# Basic_diff_probe.net
KiCad netlist of a schematic drawn in Altium Designer
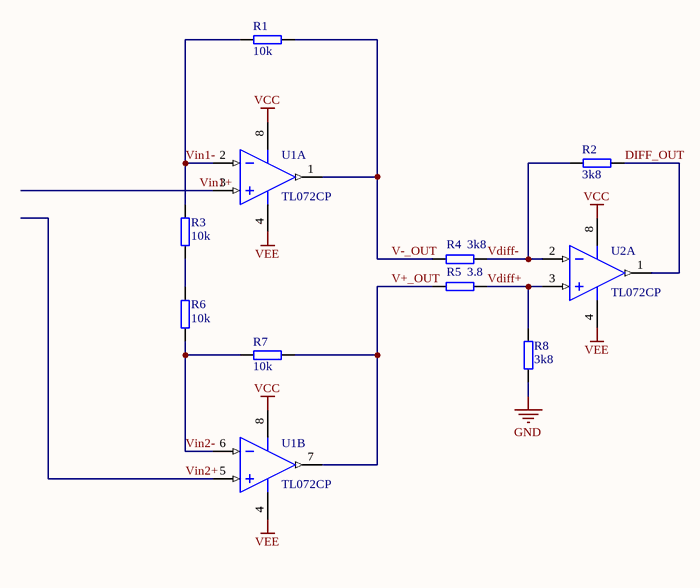
[diagram p0: Basic diff probe.SchDoc]

(export (version "E")
  (design (tool "Eeschema 10.0.6"))
  (components
    (comp (ref "R1")
      (value "10k")
      (footprint "C_CERAMIC_TH_P5.08mm")
      (description "TH, Through Hole")
      (libsource (lib "DiffProbe") (part "Resistor"))
    )
    (comp (ref "R2")
      (value "3k8")
      (footprint "C_CERAMIC_TH_P5.08mm")
      (description "TH, Through Hole")
      (libsource (lib "DiffProbe") (part "Resistor"))
    )
    (comp (ref "R3")
      (value "10k")
      (footprint "C_CERAMIC_TH_P5.08mm")
      (description "TH, Through Hole")
      (libsource (lib "DiffProbe") (part "Resistor"))
    )
    (comp (ref "R4")
      (value "3k8")
      (footprint "C_CERAMIC_TH_P5.08mm")
      (description "TH, Through Hole")
      (libsource (lib "DiffProbe") (part "Resistor"))
    )
    (comp (ref "R5")
      (value "3.8")
      (footprint "C_CERAMIC_TH_P5.08mm")
      (description "TH, Through Hole")
      (libsource (lib "DiffProbe") (part "Resistor"))
    )
    (comp (ref "R6")
      (value "10k")
      (footprint "C_CERAMIC_TH_P5.08mm")
      (description "TH, Through Hole")
      (libsource (lib "DiffProbe") (part "Resistor"))
    )
    (comp (ref "R7")
      (value "10k")
      (footprint "C_CERAMIC_TH_P5.08mm")
      (description "TH, Through Hole")
      (libsource (lib "DiffProbe") (part "Resistor"))
    )
    (comp (ref "R8")
      (value "3k8")
      (footprint "C_CERAMIC_TH_P5.08mm")
      (description "TH, Through Hole")
      (libsource (lib "DiffProbe") (part "Resistor"))
    )
    (comp (ref "U1")
      (value "TL072CP")
      (footprint "P0008A")
      (description "IC OPAMP JFET 3MHZ 8DIP")
      (fields (field (name "MANUFACTURER") "Texas Instruments"))
      (libsource (lib "DiffProbe") (part "TL072CP"))
    )
    (comp (ref "U2")
      (value "TL072CP")
      (footprint "P0008A")
      (description "IC OPAMP JFET 3MHZ 8DIP")
      (fields (field (name "MANUFACTURER") "Texas Instruments"))
      (libsource (lib "DiffProbe") (part "TL072CP"))
    )
  )
  (nets
    (net (code "1") (name "/DIFF_OUT") (class "Default")
      (node (ref "R2") (pin "2") (pinfunction "2_2") (pintype "passive"))
      (node (ref "U2") (pin "1") (pinfunction "OUT1_1") (pintype "output"))
    )
    (net (code "2") (name "/V+_OUT") (class "Default")
      (node (ref "R5") (pin "1") (pinfunction "1_1") (pintype "passive"))
      (node (ref "R7") (pin "2") (pinfunction "2_2") (pintype "passive"))
      (node (ref "U1") (pin "7") (pinfunction "OUT2_7") (pintype "output"))
    )
    (net (code "3") (name "/V-_OUT") (class "Default")
      (node (ref "R1") (pin "2") (pinfunction "2_2") (pintype "passive"))
      (node (ref "R4") (pin "1") (pinfunction "1_1") (pintype "passive"))
      (node (ref "U1") (pin "1") (pinfunction "OUT1_1") (pintype "output"))
    )
    (net (code "4") (name "/Vdiff+") (class "Default")
      (node (ref "R5") (pin "2") (pinfunction "2_2") (pintype "passive"))
      (node (ref "R8") (pin "2") (pinfunction "2_2") (pintype "passive"))
      (node (ref "U2") (pin "3") (pinfunction "IN1+_3") (pintype "input"))
    )
    (net (code "5") (name "/Vdiff-") (class "Default")
      (node (ref "R2") (pin "1") (pinfunction "1_1") (pintype "passive"))
      (node (ref "R4") (pin "2") (pinfunction "2_2") (pintype "passive"))
      (node (ref "U2") (pin "2") (pinfunction "IN1-_2") (pintype "input"))
    )
    (net (code "6") (name "/Vin1+") (class "Default")
      (node (ref "U1") (pin "3") (pinfunction "IN1+_3") (pintype "input"))
    )
    (net (code "7") (name "/Vin1-") (class "Default")
      (node (ref "R1") (pin "1") (pinfunction "1_1") (pintype "passive"))
      (node (ref "R3") (pin "2") (pinfunction "2_2") (pintype "passive"))
      (node (ref "U1") (pin "2") (pinfunction "IN1-_2") (pintype "input"))
    )
    (net (code "8") (name "/Vin2+") (class "Default")
      (node (ref "U1") (pin "5") (pinfunction "IN1+_5") (pintype "input"))
    )
    (net (code "9") (name "/Vin2-") (class "Default")
      (node (ref "R6") (pin "1") (pinfunction "1_1") (pintype "passive"))
      (node (ref "R7") (pin "1") (pinfunction "1_1") (pintype "passive"))
      (node (ref "U1") (pin "6") (pinfunction "IN1-_6") (pintype "input"))
    )
    (net (code "10") (name "GND") (class "Default")
      (node (ref "R8") (pin "1") (pinfunction "1_1") (pintype "passive"))
    )
    (net (code "11") (name "Net-(R3-Pad1)") (class "Default")
      (node (ref "R3") (pin "1") (pinfunction "1_1") (pintype "passive"))
      (node (ref "R6") (pin "2") (pinfunction "2_2") (pintype "passive"))
    )
    (net (code "12") (name "VCC") (class "Default")
      (node (ref "U1") (pin "8") (pinfunction "VCC+_8") (pintype "power_in"))
      (node (ref "U2") (pin "8") (pinfunction "VCC+_8") (pintype "power_in"))
    )
    (net (code "13") (name "VEE") (class "Default")
      (node (ref "U1") (pin "4") (pinfunction "VCC-_4") (pintype "power_in"))
      (node (ref "U2") (pin "4") (pinfunction "VCC-_4") (pintype "power_in"))
    )
  )
)
